# Schematic.net
KiCad netlist of a schematic drawn in Altium Designer
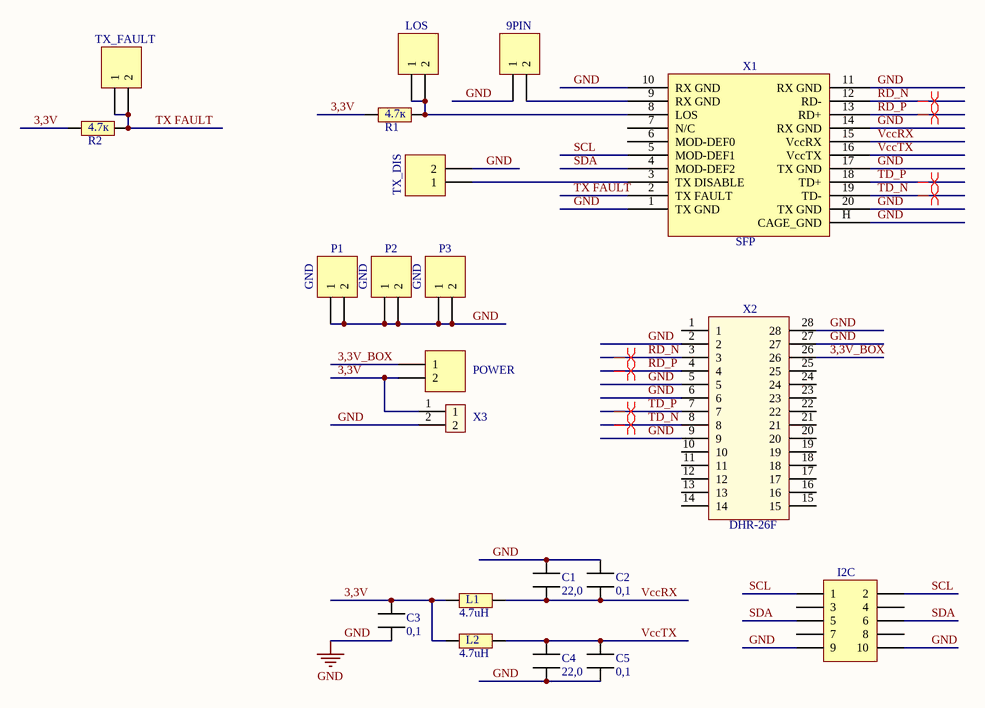
[diagram p0: Schematic.SchDoc]

(export (version "E")
  (design (tool "Eeschema 10.0.6"))
  (components
    (comp (ref "9PIN")
      (value "Header 2")
      (footprint "HDR1X2")
      (description "Header, 2-Pin")
      (fields (field (name "PUBLISHER") "Altium Limited"))
      (libsource (lib "Miscellaneous Connectors") (part "Header 2"))
    )
    (comp (ref "C1") (value "22,0") (footprint "Cap_BIG") (libsource (lib "Schlib") (part "CAP_BIG")))
    (comp (ref "C2") (value "0,1") (footprint "CAP_SMALL") (libsource (lib "Schlib") (part "CAP_SMALL")))
    (comp (ref "C3") (value "0,1") (footprint "CAP_SMALL") (libsource (lib "Schlib") (part "CAP_SMALL")))
    (comp (ref "C4") (value "22,0") (footprint "Cap_BIG") (libsource (lib "Schlib") (part "CAP_BIG")))
    (comp (ref "C5") (value "0,1") (footprint "CAP_SMALL") (libsource (lib "Schlib") (part "CAP_SMALL")))
    (comp (ref "I2C")
      (value "Header 5X2")
      (footprint "HDR2X5")
      (description "Header, 5-Pin, Dual row")
      (fields (field (name "PUBLISHER") "Altium Limited"))
      (libsource (lib "Miscellaneous Connectors") (part "Header 5X2"))
    )
    (comp (ref "L1") (value "4.7uH") (footprint "RES") (libsource (lib "Schlib") (part "RES")))
    (comp (ref "L2") (value "4.7uH") (footprint "RES") (libsource (lib "Schlib") (part "RES")))
    (comp (ref "LOS")
      (value "Header 2")
      (footprint "HDR1X2")
      (description "Header, 2-Pin")
      (fields (field (name "PUBLISHER") "Altium Limited"))
      (libsource (lib "Miscellaneous Connectors") (part "Header 2"))
    )
    (comp (ref "P1")
      (value "GND")
      (footprint "HDR1X2")
      (description "Header, 2-Pin")
      (fields (field (name "PUBLISHER") "Altium Limited"))
      (libsource (lib "Miscellaneous Connectors") (part "Header 2"))
    )
    (comp (ref "P2")
      (value "GND")
      (footprint "HDR1X2")
      (description "Header, 2-Pin")
      (fields (field (name "PUBLISHER") "Altium Limited"))
      (libsource (lib "Miscellaneous Connectors") (part "Header 2"))
    )
    (comp (ref "P3")
      (value "GND")
      (footprint "HDR1X2")
      (description "Header, 2-Pin")
      (fields (field (name "PUBLISHER") "Altium Limited"))
      (libsource (lib "Miscellaneous Connectors") (part "Header 2"))
    )
    (comp (ref "POWER")
      (value "Header 2")
      (footprint "HDR1X2")
      (description "Header, 2-Pin")
      (fields (field (name "PUBLISHER") "Altium Limited"))
      (libsource (lib "") (part "Header 2_2"))
    )
    (comp (ref "R1") (value "4.7к") (footprint "RES") (libsource (lib "Schlib") (part "RES")))
    (comp (ref "R2") (value "4.7к") (footprint "RES") (libsource (lib "Schlib") (part "RES")))
    (comp (ref "TX_DIS")
      (value "Header 2")
      (footprint "HDR1X2")
      (description "Header, 2-Pin")
      (fields (field (name "PUBLISHER") "Altium Limited"))
      (libsource (lib "") (part "Header 2_1"))
    )
    (comp (ref "TX_FAULT")
      (value "Header 2")
      (footprint "HDR1X2")
      (description "Header, 2-Pin")
      (fields (field (name "PUBLISHER") "Altium Limited"))
      (libsource (lib "Miscellaneous Connectors") (part "Header 2"))
    )
    (comp (ref "X1") (value "SFP") (footprint "SFP-20pin") (libsource (lib "MIT_Schlib") (part "SFP-20pin")))
    (comp (ref "X2") (value "DHR-26F") (footprint "DHR-26F") (libsource (lib "Schlib") (part "DHR-26F")))
    (comp (ref "X3") (value "KL_2") (footprint "KLEMMNIK_2") (libsource (lib "Schlib") (part "KLEMMNIK_2")))
  )
  (nets
    (net (code "1") (name "/3,3V") (class "Default")
      (node (ref "C3") (pin "2") (pinfunction "2_2") (pintype "passive"))
      (node (ref "L1") (pin "1") (pinfunction "1_1") (pintype "passive"))
      (node (ref "L2") (pin "1") (pinfunction "1_1") (pintype "passive"))
      (node (ref "POWER") (pin "2") (pinfunction "2_2") (pintype "passive"))
      (node (ref "R1") (pin "1") (pinfunction "1_1") (pintype "passive"))
      (node (ref "R2") (pin "1") (pinfunction "1_1") (pintype "passive"))
      (node (ref "X3") (pin "1") (pinfunction "1_1") (pintype "passive"))
    )
    (net (code "2") (name "/3,3V_BOX") (class "Default")
      (node (ref "POWER") (pin "1") (pinfunction "1_1") (pintype "passive"))
      (node (ref "X2") (pin "26") (pinfunction "26_26") (pintype "passive"))
    )
    (net (code "3") (name "/RD_N") (class "Default")
      (node (ref "X1") (pin "12") (pinfunction "RD-_12") (pintype "passive"))
      (node (ref "X2") (pin "3") (pinfunction "3_3") (pintype "passive"))
    )
    (net (code "4") (name "/RD_P") (class "Default")
      (node (ref "X1") (pin "13") (pinfunction "RD+_13") (pintype "passive"))
      (node (ref "X2") (pin "4") (pinfunction "4_4") (pintype "passive"))
    )
    (net (code "5") (name "/SCL") (class "Default")
      (node (ref "I2C") (pin "1") (pinfunction "1_1") (pintype "passive"))
      (node (ref "I2C") (pin "2") (pinfunction "2_2") (pintype "passive"))
      (node (ref "X1") (pin "5") (pinfunction "MOD-DEF1_5") (pintype "passive"))
    )
    (net (code "6") (name "/SDA") (class "Default")
      (node (ref "I2C") (pin "5") (pinfunction "5_5") (pintype "passive"))
      (node (ref "I2C") (pin "6") (pinfunction "6_6") (pintype "passive"))
      (node (ref "X1") (pin "4") (pinfunction "MOD-DEF2_4") (pintype "passive"))
    )
    (net (code "7") (name "/TD_N") (class "Default")
      (node (ref "X1") (pin "19") (pinfunction "TD-_19") (pintype "passive"))
      (node (ref "X2") (pin "8") (pinfunction "8_8") (pintype "passive"))
    )
    (net (code "8") (name "/TD_P") (class "Default")
      (node (ref "X1") (pin "18") (pinfunction "TD+_18") (pintype "passive"))
      (node (ref "X2") (pin "7") (pinfunction "7_7") (pintype "passive"))
    )
    (net (code "9") (name "/TX FAULT") (class "Default")
      (node (ref "R2") (pin "2") (pinfunction "2_2") (pintype "passive"))
      (node (ref "TX_FAULT") (pin "1") (pinfunction "1_1") (pintype "passive"))
      (node (ref "TX_FAULT") (pin "2") (pinfunction "2_2") (pintype "passive"))
      (node (ref "X1") (pin "2") (pinfunction "TX_FAULT_2") (pintype "passive"))
    )
    (net (code "10") (name "/VccRX") (class "Default")
      (node (ref "C1") (pin "1") (pinfunction "1_1") (pintype "passive"))
      (node (ref "C2") (pin "1") (pinfunction "1_1") (pintype "passive"))
      (node (ref "L1") (pin "2") (pinfunction "2_2") (pintype "passive"))
      (node (ref "X1") (pin "15") (pinfunction "VccRX_15") (pintype "passive"))
    )
    (net (code "11") (name "/VccTX") (class "Default")
      (node (ref "C4") (pin "2") (pinfunction "2_2") (pintype "passive"))
      (node (ref "C5") (pin "2") (pinfunction "2_2") (pintype "passive"))
      (node (ref "L2") (pin "2") (pinfunction "2_2") (pintype "passive"))
      (node (ref "X1") (pin "16") (pinfunction "VccTX_16") (pintype "passive"))
    )
    (net (code "12") (name "GND") (class "Default")
      (node (ref "9PIN") (pin "1") (pinfunction "1_1") (pintype "passive"))
      (node (ref "C1") (pin "2") (pinfunction "2_2") (pintype "passive"))
      (node (ref "C2") (pin "2") (pinfunction "2_2") (pintype "passive"))
      (node (ref "C3") (pin "1") (pinfunction "1_1") (pintype "passive"))
      (node (ref "C4") (pin "1") (pinfunction "1_1") (pintype "passive"))
      (node (ref "C5") (pin "1") (pinfunction "1_1") (pintype "passive"))
      (node (ref "I2C") (pin "10") (pinfunction "10_10") (pintype "passive"))
      (node (ref "I2C") (pin "9") (pinfunction "9_9") (pintype "passive"))
      (node (ref "P1") (pin "1") (pinfunction "1_1") (pintype "passive"))
      (node (ref "P1") (pin "2") (pinfunction "2_2") (pintype "passive"))
      (node (ref "P2") (pin "1") (pinfunction "1_1") (pintype "passive"))
      (node (ref "P2") (pin "2") (pinfunction "2_2") (pintype "passive"))
      (node (ref "P3") (pin "1") (pinfunction "1_1") (pintype "passive"))
      (node (ref "P3") (pin "2") (pinfunction "2_2") (pintype "passive"))
      (node (ref "TX_DIS") (pin "2") (pinfunction "2_2") (pintype "passive"))
      (node (ref "X1") (pin "1") (pinfunction "TX_GND_1") (pintype "passive"))
      (node (ref "X1") (pin "10") (pinfunction "RX_GND_10") (pintype "passive"))
      (node (ref "X1") (pin "11") (pinfunction "RX_GND_11") (pintype "passive"))
      (node (ref "X1") (pin "14") (pinfunction "RX_GND_14") (pintype "passive"))
      (node (ref "X1") (pin "17") (pinfunction "TX_GND_17") (pintype "passive"))
      (node (ref "X1") (pin "20") (pinfunction "TX_GND_20") (pintype "passive"))
      (node (ref "X1") (pin "H") (pinfunction "CAGE_GND_H") (pintype "passive"))
      (node (ref "X2") (pin "2") (pinfunction "2_2") (pintype "passive"))
      (node (ref "X2") (pin "27") (pinfunction "27_27") (pintype "passive"))
      (node (ref "X2") (pin "28") (pinfunction "28_28") (pintype "passive"))
      (node (ref "X2") (pin "5") (pinfunction "5_5") (pintype "passive"))
      (node (ref "X2") (pin "6") (pinfunction "6_6") (pintype "passive"))
      (node (ref "X2") (pin "9") (pinfunction "9_9") (pintype "passive"))
      (node (ref "X3") (pin "2") (pinfunction "2_2") (pintype "passive"))
    )
    (net (code "13") (name "Net-(9PIN-Pad2)") (class "Default")
      (node (ref "9PIN") (pin "2") (pinfunction "2_2") (pintype "passive"))
      (node (ref "X1") (pin "9") (pinfunction "RX_GND_9") (pintype "passive"))
    )
    (net (code "14") (name "Net-(X1-LOS)") (class "Default")
      (node (ref "LOS") (pin "1") (pinfunction "1_1") (pintype "passive"))
      (node (ref "LOS") (pin "2") (pinfunction "2_2") (pintype "passive"))
      (node (ref "R1") (pin "2") (pinfunction "2_2") (pintype "passive"))
      (node (ref "X1") (pin "8") (pinfunction "LOS_8") (pintype "passive"))
    )
    (net (code "15") (name "Net-(X1-TX_DISABLE)") (class "Default")
      (node (ref "TX_DIS") (pin "1") (pinfunction "1_1") (pintype "passive"))
      (node (ref "X1") (pin "3") (pinfunction "TX_DISABLE_3") (pintype "passive"))
    )
    (net (code "16") (name "unconnected-(I2C-Pad3)") (class "Default")
      (node (ref "I2C") (pin "3") (pinfunction "3_3") (pintype "passive"))
    )
    (net (code "17") (name "unconnected-(I2C-Pad4)") (class "Default")
      (node (ref "I2C") (pin "4") (pinfunction "4_4") (pintype "passive"))
    )
    (net (code "18") (name "unconnected-(I2C-Pad7)") (class "Default")
      (node (ref "I2C") (pin "7") (pinfunction "7_7") (pintype "passive"))
    )
    (net (code "19") (name "unconnected-(I2C-Pad8)") (class "Default")
      (node (ref "I2C") (pin "8") (pinfunction "8_8") (pintype "passive"))
    )
    (net (code "20") (name "unconnected-(X1-MOD-DEF0-Pad6)") (class "Default")
      (node (ref "X1") (pin "6") (pinfunction "MOD-DEF0_6") (pintype "passive"))
    )
    (net (code "21") (name "unconnected-(X1-N{slash}C-Pad7)") (class "Default")
      (node (ref "X1") (pin "7") (pinfunction "N/C_7") (pintype "passive"))
    )
    (net (code "22") (name "unconnected-(X2-Pad1)") (class "Default")
      (node (ref "X2") (pin "1") (pinfunction "1_1") (pintype "passive"))
    )
    (net (code "23") (name "unconnected-(X2-Pad10)") (class "Default")
      (node (ref "X2") (pin "10") (pinfunction "10_10") (pintype "passive"))
    )
    (net (code "24") (name "unconnected-(X2-Pad11)") (class "Default")
      (node (ref "X2") (pin "11") (pinfunction "11_11") (pintype "passive"))
    )
    (net (code "25") (name "unconnected-(X2-Pad12)") (class "Default")
      (node (ref "X2") (pin "12") (pinfunction "12_12") (pintype "passive"))
    )
    (net (code "26") (name "unconnected-(X2-Pad13)") (class "Default")
      (node (ref "X2") (pin "13") (pinfunction "13_13") (pintype "passive"))
    )
    (net (code "27") (name "unconnected-(X2-Pad14)") (class "Default")
      (node (ref "X2") (pin "14") (pinfunction "14_14") (pintype "passive"))
    )
    (net (code "28") (name "unconnected-(X2-Pad15)") (class "Default")
      (node (ref "X2") (pin "15") (pinfunction "15_15") (pintype "passive"))
    )
    (net (code "29") (name "unconnected-(X2-Pad16)") (class "Default")
      (node (ref "X2") (pin "16") (pinfunction "16_16") (pintype "passive"))
    )
    (net (code "30") (name "unconnected-(X2-Pad17)") (class "Default")
      (node (ref "X2") (pin "17") (pinfunction "17_17") (pintype "passive"))
    )
    (net (code "31") (name "unconnected-(X2-Pad18)") (class "Default")
      (node (ref "X2") (pin "18") (pinfunction "18_18") (pintype "passive"))
    )
    (net (code "32") (name "unconnected-(X2-Pad19)") (class "Default")
      (node (ref "X2") (pin "19") (pinfunction "19_19") (pintype "passive"))
    )
    (net (code "33") (name "unconnected-(X2-Pad20)") (class "Default")
      (node (ref "X2") (pin "20") (pinfunction "20_20") (pintype "passive"))
    )
    (net (code "34") (name "unconnected-(X2-Pad21)") (class "Default")
      (node (ref "X2") (pin "21") (pinfunction "21_21") (pintype "passive"))
    )
    (net (code "35") (name "unconnected-(X2-Pad22)") (class "Default")
      (node (ref "X2") (pin "22") (pinfunction "22_22") (pintype "passive"))
    )
    (net (code "36") (name "unconnected-(X2-Pad23)") (class "Default")
      (node (ref "X2") (pin "23") (pinfunction "23_23") (pintype "passive"))
    )
    (net (code "37") (name "unconnected-(X2-Pad24)") (class "Default")
      (node (ref "X2") (pin "24") (pinfunction "24_24") (pintype "passive"))
    )
    (net (code "38") (name "unconnected-(X2-Pad25)") (class "Default")
      (node (ref "X2") (pin "25") (pinfunction "25_25") (pintype "passive"))
    )
  )
)
